# Charger.net
KiCad netlist of a schematic drawn in Altium Designer
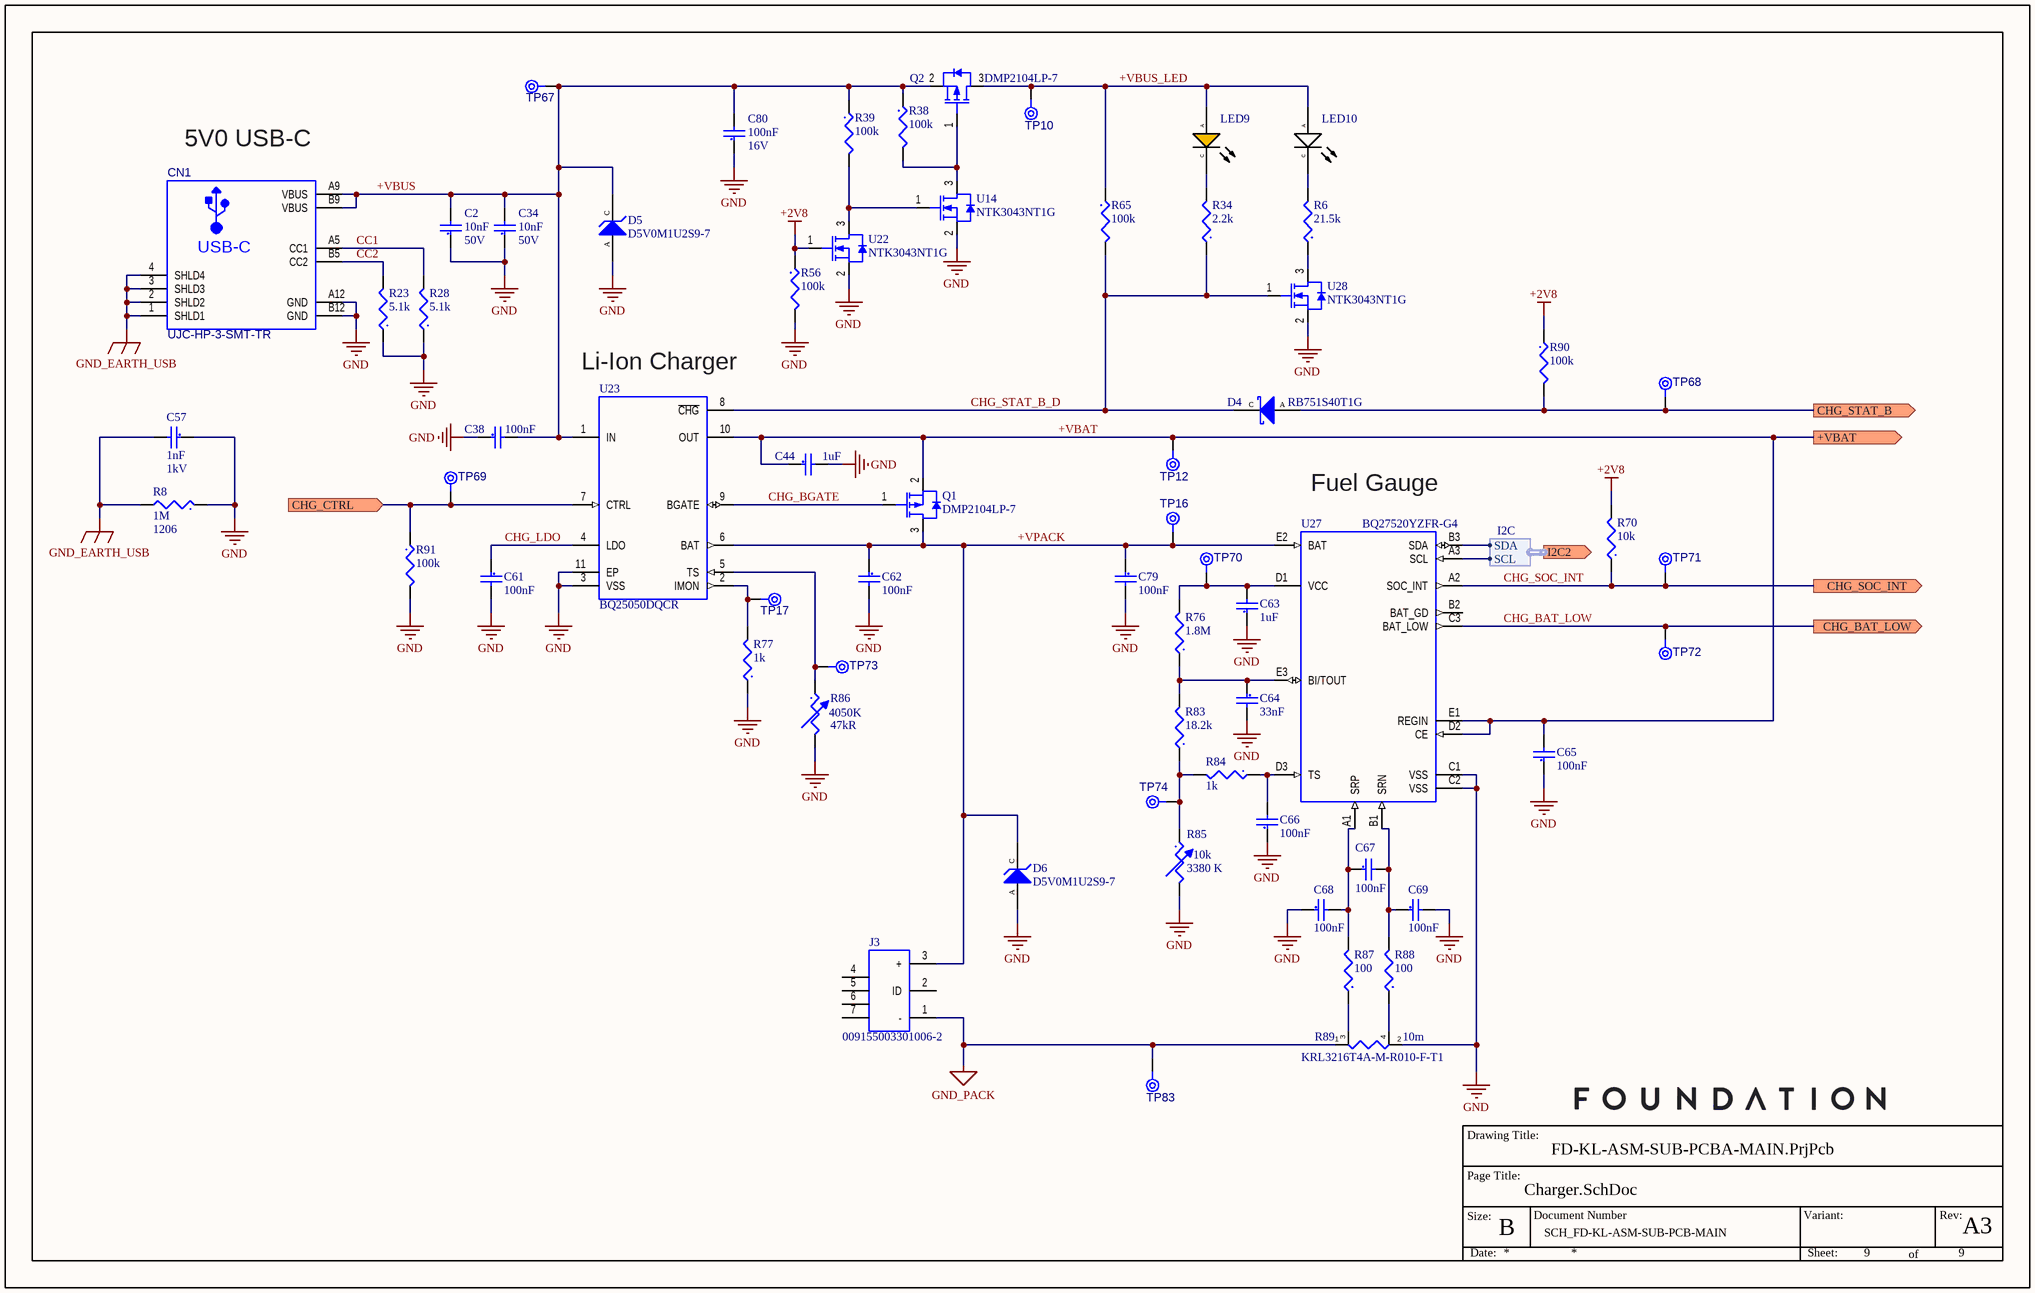
[diagram p0: Charger.SchDoc]

(export (version "E")
  (design (tool "Eeschema 10.0.6"))
  (components
    (comp (ref "C2")
      (value "CAP CER 0.01uF 50V 10% X7R 0402")
      (footprint "CAPC0402(1005)55_L")
      (description "10000pF ±10% 50V Ceramic Capacitor X7R 0402 (1005 Metric)")
      (fields
        (field (name "CAPACITANCE") "10nF")
        (field (name "TOLERANCE") "10%")
        (field (name "VOLTAGE") "50V")
      )
      (libsource (lib "Altium Concord Pro on A365") (part "CAP-NP-2"))
    )
    (comp (ref "C34")
      (value "CAP CER 0.01uF 50V 10% X7R 0402")
      (footprint "CAPC0402(1005)55_L")
      (description "10000pF ±10% 50V Ceramic Capacitor X7R 0402 (1005 Metric)")
      (fields
        (field (name "CAPACITANCE") "10nF")
        (field (name "TOLERANCE") "10%")
        (field (name "VOLTAGE") "50V")
      )
      (libsource (lib "Altium Concord Pro on A365") (part "CAP-NP-2"))
    )
    (comp (ref "C38")
      (value "CAP CER 0.1uF 16V 10% X7R 0402")
      (footprint "CAPC0402(1005)55_L")
      (description "0.1µF ±10% 16V Ceramic Capacitor X7R 0402 (1005 Metric)")
      (fields
        (field (name "CAPACITANCE") "100nF")
        (field (name "TOLERANCE") "10%")
        (field (name "VOLTAGE") "16V")
      )
      (libsource (lib "Altium Concord Pro on A365") (part "CAP-NP-2"))
    )
    (comp (ref "C44")
      (value "CAP CER 1uF 25V 10% X5R 0402")
      (footprint "CAPC0402(1005)55_L")
      (description "1uF ±10% 25V Ceramic Capacitor X5R 0402 (1005 Metric)")
      (fields (field (name "CAPACITANCE") "1uF"))
      (libsource (lib "Altium Concord Pro on A365") (part "CAP-NP-2"))
    )
    (comp (ref "C57")
      (value "CAP CER 1000pF 1000V 10% X7R 0805")
      (footprint "CAPC0805(2012)145_N")
      (description "1000pF ±10% 1000V (1kV) Ceramic Capacitor X7R 0805 (2012 Metric)")
      (fields
        (field (name "CAPACITANCE") "1nF")
        (field (name "VOLTAGE RATING (DC)") "1kV")
        (field (name "TOLERANCE") "10%")
      )
      (libsource (lib "Altium Concord Pro on A365") (part "CAP-NP-2"))
    )
    (comp (ref "C61")
      (value "CAP CER 0.1uF 16V 10% X7R 0402")
      (footprint "CAPC0402(1005)55_L")
      (description "0.1µF ±10% 16V Ceramic Capacitor X7R 0402 (1005 Metric)")
      (fields
        (field (name "CAPACITANCE") "100nF")
        (field (name "TOLERANCE") "10%")
        (field (name "VOLTAGE") "16V")
      )
      (libsource (lib "Altium Concord Pro on A365") (part "CAP-NP-2"))
    )
    (comp (ref "C62")
      (value "CAP CER 0.1uF 16V 10% X7R 0402")
      (footprint "CAPC0402(1005)55_L")
      (description "0.1µF ±10% 16V Ceramic Capacitor X7R 0402 (1005 Metric)")
      (fields
        (field (name "CAPACITANCE") "100nF")
        (field (name "TOLERANCE") "10%")
        (field (name "VOLTAGE") "16V")
      )
      (libsource (lib "Altium Concord Pro on A365") (part "CAP-NP-2"))
    )
    (comp (ref "C63")
      (value "CAP CER 1uF 25V 10% X5R 0402")
      (footprint "CAPC0402(1005)55_L")
      (description "1uF ±10% 25V Ceramic Capacitor X5R 0402 (1005 Metric)")
      (fields (field (name "CAPACITANCE") "1uF"))
      (libsource (lib "Altium Concord Pro on A365") (part "CAP-NP-2"))
    )
    (comp (ref "C64")
      (value "CAP CER 0.033uF 25V 10% X7R 0402")
      (footprint "CAPC0402(1005)55_L")
      (description "0.033µF ±10% 25V Ceramic Capacitor X7R 0402 (1005 Metric)")
      (fields (field (name "CAPACITANCE") "33nF"))
      (libsource (lib "Altium Concord Pro on A365") (part "CAP-NP-2"))
    )
    (comp (ref "C65")
      (value "CAP CER 0.1uF 16V 10% X7R 0402")
      (footprint "CAPC0402(1005)55_L")
      (description "0.1µF ±10% 16V Ceramic Capacitor X7R 0402 (1005 Metric)")
      (fields
        (field (name "CAPACITANCE") "100nF")
        (field (name "TOLERANCE") "10%")
        (field (name "VOLTAGE") "16V")
      )
      (libsource (lib "Altium Concord Pro on A365") (part "CAP-NP-2"))
    )
    (comp (ref "C66")
      (value "CAP CER 0.1uF 16V 10% X7R 0402")
      (footprint "CAPC0402(1005)55_L")
      (description "0.1µF ±10% 16V Ceramic Capacitor X7R 0402 (1005 Metric)")
      (fields
        (field (name "CAPACITANCE") "100nF")
        (field (name "TOLERANCE") "10%")
        (field (name "VOLTAGE") "16V")
      )
      (libsource (lib "Altium Concord Pro on A365") (part "CAP-NP-2"))
    )
    (comp (ref "C67")
      (value "CAP CER 0.1uF 16V 10% X7R 0402")
      (footprint "CAPC0402(1005)55_L")
      (description "0.1µF ±10% 16V Ceramic Capacitor X7R 0402 (1005 Metric)")
      (fields
        (field (name "CAPACITANCE") "100nF")
        (field (name "TOLERANCE") "10%")
        (field (name "VOLTAGE") "16V")
      )
      (libsource (lib "Altium Concord Pro on A365") (part "CAP-NP-2"))
    )
    (comp (ref "C68")
      (value "CAP CER 0.1uF 16V 10% X7R 0402")
      (footprint "CAPC0402(1005)55_L")
      (description "0.1µF ±10% 16V Ceramic Capacitor X7R 0402 (1005 Metric)")
      (fields
        (field (name "CAPACITANCE") "100nF")
        (field (name "TOLERANCE") "10%")
        (field (name "VOLTAGE") "16V")
      )
      (libsource (lib "Altium Concord Pro on A365") (part "CAP-NP-2"))
    )
    (comp (ref "C69")
      (value "CAP CER 0.1uF 16V 10% X7R 0402")
      (footprint "CAPC0402(1005)55_L")
      (description "0.1µF ±10% 16V Ceramic Capacitor X7R 0402 (1005 Metric)")
      (fields
        (field (name "CAPACITANCE") "100nF")
        (field (name "TOLERANCE") "10%")
        (field (name "VOLTAGE") "16V")
      )
      (libsource (lib "Altium Concord Pro on A365") (part "CAP-NP-2"))
    )
    (comp (ref "C79")
      (value "CAP CER 0.1uF 16V 10% X7R 0402")
      (footprint "CAPC0402(1005)55_L")
      (description "0.1µF ±10% 16V Ceramic Capacitor X7R 0402 (1005 Metric)")
      (fields
        (field (name "CAPACITANCE") "100nF")
        (field (name "TOLERANCE") "10%")
        (field (name "VOLTAGE") "16V")
      )
      (libsource (lib "Altium Concord Pro on A365") (part "CAP-NP-2"))
    )
    (comp (ref "C80")
      (value "CAP CER 0.1uF 16V 10% X7R 0402")
      (footprint "CAPC0402(1005)55_L")
      (description "0.1µF ±10% 16V Ceramic Capacitor X7R 0402 (1005 Metric)")
      (fields
        (field (name "CAPACITANCE") "100nF")
        (field (name "TOLERANCE") "10%")
        (field (name "VOLTAGE") "16V")
      )
      (libsource (lib "Altium Concord Pro on A365") (part "CAP-NP-2"))
    )
    (comp (ref "CN1")
      (value "UJC-HP-3-SMT-TR")
      (footprint "CUI - UJC-HP-3-SMT_V")
      (libsource (lib "Altium Concord Pro on A365") (part "USBC-6-4S"))
    )
    (comp (ref "D4")
      (value "RB751S40T1G")
      (footprint "ON - SOD-523_V")
      (description "Diode Schottky 30V 30mA (DC) Surface Mount SOD-523")
      (libsource (lib "Altium Concord Pro on A365") (part "DSKY-AC-2"))
    )
    (comp (ref "D5")
      (value "D5V0M1U2S9-7")
      (footprint "DIOD - SOD-923_V")
      (description "12V Clamp 9A (8/20µs) Ipp Tvs Diode Surface Mount SOD-923")
      (libsource (lib "Altium Concord Pro on A365") (part "DZEN-AC-2"))
    )
    (comp (ref "D6")
      (value "D5V0M1U2S9-7")
      (footprint "DIOD - SOD-923_V")
      (description "12V Clamp 9A (8/20µs) Ipp Tvs Diode Surface Mount SOD-923")
      (libsource (lib "Altium Concord Pro on A365") (part "DZEN-AC-2"))
    )
    (comp (ref "J3")
      (value "009155003301006-2")
      (footprint "AVX - 009155003301006_V")
      (description "3 Position Spring Battery Contact Connector Surface Mount, Right Angle")
      (libsource (lib "Altium Concord Pro on A365") (part "009155003301006-2"))
    )
    (comp (ref "LED9")
      (value "IN-S63AT5A")
      (footprint "LEDC0603(1608)65_L")
      (description "Amber 605nm LED Indication - Discrete 1.9V 0603 (1608 Metric)")
      (libsource (lib "Altium Concord Pro on A365") (part "LED-AMBER-AC-2"))
    )
    (comp (ref "LED10")
      (value "IN-S63AT5UW")
      (footprint "LEDC0603(1608)65_L")
      (description "White - LED Indication - Discrete 3V 0603 (1608 Metric)")
      (libsource (lib "Altium Concord Pro on A365") (part "LED-WHITE-AC-2"))
    )
    (comp (ref "Q1")
      (value "DMP2104LP-7")
      (footprint "DIOD - XDFN-3_V")
      (description "P-Channel 20 V 1.5A (Ta) 500mW (Ta) Surface Mount 3-DFN1411 (1.4x1.1)")
      (libsource (lib "Altium Concord Pro on A365") (part "PMOS-GSD-3"))
    )
    (comp (ref "Q2")
      (value "DMP2104LP-7")
      (footprint "DIOD - XDFN-3_V")
      (description "P-Channel 20 V 1.5A (Ta) 500mW (Ta) Surface Mount 3-DFN1411 (1.4x1.1)")
      (libsource (lib "Altium Concord Pro on A365") (part "PMOS-GSD-3"))
    )
    (comp (ref "R6")
      (value "RES 21.5K 1/16W 1% 0402")
      (footprint "RESC0402(1005)_L")
      (description "21.5 kOhms ±1% 0.063W, 1/16W Chip Resistor 0402 (1005 Metric)")
      (fields (field (name "RESISTANCE") "21.5k") (field (name "TOLERANCE") "1%"))
      (libsource (lib "Altium Concord Pro on A365") (part "RES-2"))
    )
    (comp (ref "R8")
      (value "RES 1.0M 1/4W 5% 1206")
      (footprint "RESC1206(3216)_L")
      (description "1 MOhms ±5% 0.25W, 1/4W Chip Resistor 1206 (3216 Metric) Moisture Resistant Thick Film")
      (fields
        (field (name "RESISTANCE") "1M")
        (field (name "TOLERANCE") "5%")
        (field (name "CASE CODE (IMPERIAL)") "1206")
      )
      (libsource (lib "Altium Concord Pro on A365") (part "RES-2"))
    )
    (comp (ref "R23")
      (value "RES 5.1K 1/16W 1% 0402")
      (footprint "RESC0402(1005)_L")
      (description "5.1 kOhms ±1% 0.063W, 1/16W Chip Resistor 0402 (1005 Metric)")
      (fields (field (name "RESISTANCE") "5.1k") (field (name "TOLERANCE") "1%"))
      (libsource (lib "Altium Concord Pro on A365") (part "RES-2"))
    )
    (comp (ref "R28")
      (value "RES 5.1K 1/16W 1% 0402")
      (footprint "RESC0402(1005)_L")
      (description "5.1 kOhms ±1% 0.063W, 1/16W Chip Resistor 0402 (1005 Metric)")
      (fields (field (name "RESISTANCE") "5.1k") (field (name "TOLERANCE") "1%"))
      (libsource (lib "Altium Concord Pro on A365") (part "RES-2"))
    )
    (comp (ref "R34")
      (value "RES 2.2K 1/16W 1% 0402")
      (footprint "RESC0402(1005)_L")
      (description "2.2 kOhms ±1% 0.063W, 1/16W Chip Resistor 0402 (1005 Metric)")
      (fields (field (name "RESISTANCE") "2.2k") (field (name "TOLERANCE") "1%"))
      (libsource (lib "Altium Concord Pro on A365") (part "RES-2"))
    )
    (comp (ref "R38")
      (value "RES 100K 1/16W 1% 0402")
      (footprint "RESC0402(1005)_L")
      (description "100 kOhms ±1% 0.063W, 1/16W Chip Resistor 0402 (1005 Metric) Automotive AEC-Q200 Thick Film")
      (fields (field (name "RESISTANCE") "100k") (field (name "TOLERANCE") "1%"))
      (libsource (lib "Altium Concord Pro on A365") (part "RES-2"))
    )
    (comp (ref "R39")
      (value "RES 100K 1/16W 1% 0402")
      (footprint "RESC0402(1005)_L")
      (description "100 kOhms ±1% 0.063W, 1/16W Chip Resistor 0402 (1005 Metric) Automotive AEC-Q200 Thick Film")
      (fields (field (name "RESISTANCE") "100k") (field (name "TOLERANCE") "1%"))
      (libsource (lib "Altium Concord Pro on A365") (part "RES-2"))
    )
    (comp (ref "R56")
      (value "RES 100K 1/16W 1% 0402")
      (footprint "RESC0402(1005)_L")
      (description "100 kOhms ±1% 0.063W, 1/16W Chip Resistor 0402 (1005 Metric) Automotive AEC-Q200 Thick Film")
      (fields (field (name "RESISTANCE") "100k") (field (name "TOLERANCE") "1%"))
      (libsource (lib "Altium Concord Pro on A365") (part "RES-2"))
    )
    (comp (ref "R65")
      (value "RES 100K 1/16W 1% 0402")
      (footprint "RESC0402(1005)_L")
      (description "100 kOhms ±1% 0.063W, 1/16W Chip Resistor 0402 (1005 Metric) Automotive AEC-Q200 Thick Film")
      (fields (field (name "RESISTANCE") "100k") (field (name "TOLERANCE") "1%"))
      (libsource (lib "Altium Concord Pro on A365") (part "RES-2"))
    )
    (comp (ref "R70")
      (value "RES 10K 1/16W 1% 0402")
      (footprint "RESC0402(1005)_L")
      (description "10 kOhms ±1% 0.063W, 1/16W Chip Resistor 0402 (1005 Metric)")
      (fields (field (name "RESISTANCE") "10k") (field (name "TOLERANCE") "1%"))
      (libsource (lib "Altium Concord Pro on A365") (part "RES-2"))
    )
    (comp (ref "R76")
      (value "RES 1.8M 1/16W 1% 0402")
      (footprint "RESC0402(1005)_L")
      (description "1.8 MOhms ±1% 0.063W, 1/16W Chip Resistor 0402 (1005 Metric)")
      (fields (field (name "RESISTANCE") "1.8M") (field (name "TOLERANCE") "1%"))
      (libsource (lib "Altium Concord Pro on A365") (part "RES-2"))
    )
    (comp (ref "R77")
      (value "RES 1.0K 1/16W 1% 0402")
      (footprint "RESC0402(1005)_L")
      (description "1 kOhms ±0.5% 0.063W, 1/16W Chip Resistor 0402 (1005 Metric) Automotive AEC-Q200 Thin Film")
      (fields (field (name "RESISTANCE") "1k") (field (name "TOLERANCE") "0.5%"))
      (libsource (lib "Altium Concord Pro on A365") (part "RES-2"))
    )
    (comp (ref "R83")
      (value "RES 18.2K 1/16W 1% 0402")
      (footprint "RESC0402(1005)_L")
      (description "18.2 kOhms ±1% 0.063W, 1/16W Chip Resistor 0402 (1005 Metric)")
      (fields (field (name "RESISTANCE") "18.2k") (field (name "TOLERANCE") "1%"))
      (libsource (lib "Altium Concord Pro on A365") (part "RES-2"))
    )
    (comp (ref "R84")
      (value "RES 1.0K 1/16W 1% 0402")
      (footprint "RESC0402(1005)_L")
      (description "1 kOhms ±0.5% 0.063W, 1/16W Chip Resistor 0402 (1005 Metric) Automotive AEC-Q200 Thin Film")
      (fields (field (name "RESISTANCE") "1k") (field (name "TOLERANCE") "0.5%"))
      (libsource (lib "Altium Concord Pro on A365") (part "RES-2"))
    )
    (comp (ref "R85")
      (value "NTCG103JF103FT1")
      (footprint "RESC0402(1005)_L")
      (description "NTC Thermistor 10k 0402 (1005 Metric)")
      (fields (field (name "RESISTANCE") "10k") (field (name "B CONSTANT [25/50°C]") "3380 K"))
      (libsource (lib "Altium Concord Pro on A365") (part "RES-ADJ-2"))
    )
    (comp (ref "R86")
      (value "NCP15WB473F03RC")
      (footprint "RESC0402(1005)_L")
      (description "NTC Thermistor 47k 0402 (1005 Metric)")
      (fields
        (field (name "RESISTANCE") "47kR")
        (field (name "B CONSTANT [25/50°C]") "4050K")
        (field (name "TOLERANCE") "1%")
      )
      (libsource (lib "Altium Concord Pro on A365") (part "RES-ADJ-2"))
    )
    (comp (ref "R87")
      (value "RES 100 OHM 1/16W 1% 0402")
      (footprint "RESC0402(1005)_L")
      (description "100 Ohms ±1% 0.063W, 1/16W Chip Resistor 0402 (1005 Metric)  Thick Film")
      (fields (field (name "RESISTANCE") "100") (field (name "TOLERANCE") "1%"))
      (libsource (lib "Altium Concord Pro on A365") (part "RES-2"))
    )
    (comp (ref "R88")
      (value "RES 100 OHM 1/16W 1% 0402")
      (footprint "RESC0402(1005)_L")
      (description "100 Ohms ±1% 0.063W, 1/16W Chip Resistor 0402 (1005 Metric)  Thick Film")
      (fields (field (name "RESISTANCE") "100") (field (name "TOLERANCE") "1%"))
      (libsource (lib "Altium Concord Pro on A365") (part "RES-2"))
    )
    (comp (ref "R89")
      (value "KRL3216T4A-M-R010-F-T1")
      (footprint "Susumu - KRL3216T4A_V")
      (description "Fixed Resistor, Metal Foil, 1W, 0.01ohm, 1% +/-Tol, 35ppm/Cel, Surface Mount, 1206")
      (fields (field (name "RESISTANCE") "10m") (field (name "TOLERANCE") "1%"))
      (libsource (lib "Altium Concord Pro on A365") (part "RES-4-13-24"))
    )
    (comp (ref "R90")
      (value "RES 100K 1/16W 1% 0402")
      (footprint "RESC0402(1005)_L")
      (description "100 kOhms ±1% 0.063W, 1/16W Chip Resistor 0402 (1005 Metric) Automotive AEC-Q200 Thick Film")
      (fields (field (name "RESISTANCE") "100k") (field (name "TOLERANCE") "1%"))
      (libsource (lib "Altium Concord Pro on A365") (part "RES-2"))
    )
    (comp (ref "R91")
      (value "RES 100K 1/16W 1% 0402")
      (footprint "RESC0402(1005)_L")
      (description "100 kOhms ±1% 0.063W, 1/16W Chip Resistor 0402 (1005 Metric) Automotive AEC-Q200 Thick Film")
      (fields (field (name "RESISTANCE") "100k") (field (name "TOLERANCE") "1%"))
      (libsource (lib "Altium Concord Pro on A365") (part "RES-2"))
    )
    (comp (ref "TP10")
      (value "TPAD8R")
      (footprint "TP08R")
      (description "0.8mm round")
      (libsource (lib "Altium Concord Pro on A365") (part "TP-R-1"))
    )
    (comp (ref "TP12")
      (value "TPAD8R")
      (footprint "TP08R")
      (description "0.8mm round")
      (libsource (lib "Altium Concord Pro on A365") (part "TP-R-1"))
    )
    (comp (ref "TP16")
      (value "TPAD8R")
      (footprint "TP08R")
      (description "0.8mm round")
      (libsource (lib "Altium Concord Pro on A365") (part "TP-R-1"))
    )
    (comp (ref "TP17")
      (value "TPAD8R")
      (footprint "TP08R")
      (description "0.8mm round")
      (libsource (lib "Altium Concord Pro on A365") (part "TP-R-1"))
    )
    (comp (ref "TP67")
      (value "TPAD8R")
      (footprint "TP08R")
      (description "0.8mm round")
      (libsource (lib "Altium Concord Pro on A365") (part "TP-R-1"))
    )
    (comp (ref "TP68")
      (value "TPAD8R")
      (footprint "TP08R")
      (description "0.8mm round")
      (libsource (lib "Altium Concord Pro on A365") (part "TP-R-1"))
    )
    (comp (ref "TP69")
      (value "TPAD8R")
      (footprint "TP08R")
      (description "0.8mm round")
      (libsource (lib "Altium Concord Pro on A365") (part "TP-R-1"))
    )
    (comp (ref "TP70")
      (value "TPAD8R")
      (footprint "TP08R")
      (description "0.8mm round")
      (libsource (lib "Altium Concord Pro on A365") (part "TP-R-1"))
    )
    (comp (ref "TP71")
      (value "TPAD8R")
      (footprint "TP08R")
      (description "0.8mm round")
      (libsource (lib "Altium Concord Pro on A365") (part "TP-R-1"))
    )
    (comp (ref "TP72")
      (value "TPAD8R")
      (footprint "TP08R")
      (description "0.8mm round")
      (libsource (lib "Altium Concord Pro on A365") (part "TP-R-1"))
    )
    (comp (ref "TP73")
      (value "TPAD8R")
      (footprint "TP08R")
      (description "0.8mm round")
      (libsource (lib "Altium Concord Pro on A365") (part "TP-R-1"))
    )
    (comp (ref "TP74")
      (value "TPAD8R")
      (footprint "TP08R")
      (description "0.8mm round")
      (libsource (lib "Altium Concord Pro on A365") (part "TP-R-1"))
    )
    (comp (ref "TP83")
      (value "TPAD8R")
      (footprint "TP08R")
      (description "0.8mm round")
      (libsource (lib "Altium Concord Pro on A365") (part "TP-R-1"))
    )
    (comp (ref "U14")
      (value "NTK3043NT1G")
      (footprint "SOT-723-3(40)_N")
      (description "N-Channel 20V 210mA (Ta) 310mW (Ta) Surface Mount SOT-723")
      (libsource (lib "Altium Concord Pro on A365") (part "NMOS-GSD-3"))
    )
    (comp (ref "U22")
      (value "NTK3043NT1G")
      (footprint "SOT-723-3(40)_N")
      (description "N-Channel 20V 210mA (Ta) 310mW (Ta) Surface Mount SOT-723")
      (libsource (lib "Altium Concord Pro on A365") (part "NMOS-GSD-3"))
    )
    (comp (ref "U23")
      (value "BQ25050DQCR")
      (footprint "TI - WSON-DQC-10_V")
      (description "Charger IC Lithium Ion 10-WSON (3x2)")
      (libsource (lib "Altium Concord Pro on A365") (part "SYM-IC-0151"))
    )
    (comp (ref "U27")
      (value "BQ27520YZFR-G4")
      (footprint "TI - DSBGA-YZF-15_V")
      (description "Battery Battery Monitor IC Lithium Ion 15-DSBGA")
      (libsource (lib "Altium Concord Pro on A365") (part "BQ27520YZFR-G4"))
    )
    (comp (ref "U28")
      (value "NTK3043NT1G")
      (footprint "SOT-723-3(40)_N")
      (description "N-Channel 20V 210mA (Ta) 310mW (Ta) Surface Mount SOT-723")
      (libsource (lib "Altium Concord Pro on A365") (part "NMOS-GSD-3"))
    )
  )
  (nets
    (net (code "2") (name "+2V8") (class "Default")
      (node (ref "R56") (pin "1") (pinfunction "1_1") (pintype "passive"))
      (node (ref "R70") (pin "2") (pinfunction "2_2") (pintype "passive"))
      (node (ref "R90") (pin "1") (pinfunction "1_1") (pintype "passive"))
      (node (ref "U22") (pin "1") (pinfunction "G_1") (pintype "passive"))
    )
    (net (code "3") (name "/+VBAT") (class "Default")
      (node (ref "C44") (pin "1") (pinfunction "1_1") (pintype "passive"))
      (node (ref "C65") (pin "2") (pinfunction "2_2") (pintype "passive"))
      (node (ref "Q1") (pin "2") (pinfunction "SOURCE_2") (pintype "passive"))
      (node (ref "TP12") (pin "1") (pinfunction "TP_1") (pintype "passive"))
      (node (ref "U23") (pin "10") (pinfunction "OUT_10") (pintype "power_in"))
      (node (ref "U27") (pin "D2") (pinfunction "CE_D2") (pintype "input"))
      (node (ref "U27") (pin "E1") (pinfunction "REGIN_E1") (pintype "passive"))
    )
    (net (code "4") (name "/+VBUS") (class "Default")
      (node (ref "C2") (pin "2") (pinfunction "2_2") (pintype "passive"))
      (node (ref "C34") (pin "2") (pinfunction "2_2") (pintype "passive"))
      (node (ref "C38") (pin "2") (pinfunction "2_2") (pintype "passive"))
      (node (ref "C80") (pin "2") (pinfunction "2_2") (pintype "passive"))
      (node (ref "CN1") (pin "A9") (pinfunction "VBUS_A9") (pintype "passive"))
      (node (ref "CN1") (pin "B9") (pinfunction "VBUS_B9") (pintype "passive"))
      (node (ref "D5") (pin "C") (pinfunction "C_C") (pintype "passive"))
      (node (ref "Q2") (pin "2") (pinfunction "SOURCE_2") (pintype "passive"))
      (node (ref "R38") (pin "1") (pinfunction "1_1") (pintype "passive"))
      (node (ref "R39") (pin "1") (pinfunction "1_1") (pintype "passive"))
      (node (ref "TP67") (pin "1") (pinfunction "TP_1") (pintype "passive"))
      (node (ref "U23") (pin "1") (pinfunction "IN_1") (pintype "power_in"))
    )
    (net (code "5") (name "/+VBUS_LED") (class "Default")
      (node (ref "LED10") (pin "A") (pinfunction "A_A") (pintype "passive"))
      (node (ref "LED9") (pin "A") (pinfunction "A_A") (pintype "passive"))
      (node (ref "Q2") (pin "3") (pinfunction "DRAIN_3") (pintype "passive"))
      (node (ref "R65") (pin "1") (pinfunction "1_1") (pintype "passive"))
      (node (ref "TP10") (pin "1") (pinfunction "TP_1") (pintype "passive"))
    )
    (net (code "6") (name "/+VPACK") (class "Default")
      (node (ref "C62") (pin "1") (pinfunction "1_1") (pintype "passive"))
      (node (ref "C79") (pin "1") (pinfunction "1_1") (pintype "passive"))
      (node (ref "D6") (pin "C") (pinfunction "C_C") (pintype "passive"))
      (node (ref "J3") (pin "3") (pinfunction "+_3") (pintype "passive"))
      (node (ref "Q1") (pin "3") (pinfunction "DRAIN_3") (pintype "passive"))
      (node (ref "TP16") (pin "1") (pinfunction "TP_1") (pintype "passive"))
      (node (ref "U23") (pin "6") (pinfunction "BAT_6") (pintype "output"))
      (node (ref "U27") (pin "E2") (pinfunction "BAT_E2") (pintype "input"))
    )
    (net (code "7") (name "/CC1") (class "Default")
      (node (ref "CN1") (pin "A5") (pinfunction "CC1_A5") (pintype "passive"))
      (node (ref "R28") (pin "2") (pinfunction "2_2") (pintype "passive"))
    )
    (net (code "8") (name "/CC2") (class "Default")
      (node (ref "CN1") (pin "B5") (pinfunction "CC2_B5") (pintype "passive"))
      (node (ref "R23") (pin "2") (pinfunction "2_2") (pintype "passive"))
    )
    (net (code "9") (name "/CHG_BAT_LOW") (class "Default")
      (node (ref "TP72") (pin "1") (pinfunction "TP_1") (pintype "passive"))
      (node (ref "U27") (pin "C3") (pinfunction "BAT_LOW_C3") (pintype "output"))
    )
    (net (code "10") (name "/CHG_BGATE") (class "Default")
      (node (ref "Q1") (pin "1") (pinfunction "GATE_1") (pintype "passive"))
      (node (ref "U23") (pin "9") (pinfunction "BGATE_9") (pintype "bidirectional"))
    )
    (net (code "11") (name "/CHG_CTRL") (class "Default")
      (node (ref "R91") (pin "1") (pinfunction "1_1") (pintype "passive"))
      (node (ref "TP69") (pin "1") (pinfunction "TP_1") (pintype "passive"))
      (node (ref "U23") (pin "7") (pinfunction "CTRL_7") (pintype "input"))
    )
    (net (code "12") (name "/CHG_LDO") (class "Default")
      (node (ref "C61") (pin "1") (pinfunction "1_1") (pintype "passive"))
      (node (ref "U23") (pin "4") (pinfunction "LDO_4") (pintype "power_in"))
    )
    (net (code "13") (name "/CHG_SOC_INT") (class "Default")
      (node (ref "R70") (pin "1") (pinfunction "1_1") (pintype "passive"))
      (node (ref "TP71") (pin "1") (pinfunction "TP_1") (pintype "passive"))
      (node (ref "U27") (pin "A2") (pinfunction "SOC_INT_A2") (pintype "output"))
    )
    (net (code "14") (name "/CHG_STAT_B") (class "Default")
      (node (ref "D4") (pin "A") (pinfunction "A_A") (pintype "passive"))
      (node (ref "R90") (pin "2") (pinfunction "2_2") (pintype "passive"))
      (node (ref "TP68") (pin "1") (pinfunction "TP_1") (pintype "passive"))
    )
    (net (code "15") (name "/CHG_STAT_B_D") (class "Default")
      (node (ref "D4") (pin "C") (pinfunction "C_C") (pintype "passive"))
      (node (ref "R34") (pin "1") (pinfunction "1_1") (pintype "passive"))
      (node (ref "R65") (pin "2") (pinfunction "2_2") (pintype "passive"))
      (node (ref "U23") (pin "8") (pinfunction "~{CHG}_8") (pintype "tri_state"))
      (node (ref "U28") (pin "1") (pinfunction "G_1") (pintype "passive"))
    )
    (net (code "16") (name "/SCL") (class "Default")
      (node (ref "U27") (pin "A3") (pinfunction "SCL_A3") (pintype "input"))
    )
    (net (code "17") (name "/SDA") (class "Default")
      (node (ref "U27") (pin "B3") (pinfunction "SDA_B3") (pintype "bidirectional"))
    )
    (net (code "19") (name "GND") (class "Default")
      (node (ref "C2") (pin "1") (pinfunction "1_1") (pintype "passive"))
      (node (ref "C34") (pin "1") (pinfunction "1_1") (pintype "passive"))
      (node (ref "C38") (pin "1") (pinfunction "1_1") (pintype "passive"))
      (node (ref "C44") (pin "2") (pinfunction "2_2") (pintype "passive"))
      (node (ref "C57") (pin "1") (pinfunction "1_1") (pintype "passive"))
      (node (ref "C61") (pin "2") (pinfunction "2_2") (pintype "passive"))
      (node (ref "C62") (pin "2") (pinfunction "2_2") (pintype "passive"))
      (node (ref "C63") (pin "1") (pinfunction "1_1") (pintype "passive"))
      (node (ref "C64") (pin "2") (pinfunction "2_2") (pintype "passive"))
      (node (ref "C65") (pin "1") (pinfunction "1_1") (pintype "passive"))
      (node (ref "C66") (pin "1") (pinfunction "1_1") (pintype "passive"))
      (node (ref "C68") (pin "1") (pinfunction "1_1") (pintype "passive"))
      (node (ref "C69") (pin "2") (pinfunction "2_2") (pintype "passive"))
      (node (ref "C79") (pin "2") (pinfunction "2_2") (pintype "passive"))
      (node (ref "C80") (pin "1") (pinfunction "1_1") (pintype "passive"))
      (node (ref "CN1") (pin "A12") (pinfunction "GND_A12") (pintype "passive"))
      (node (ref "CN1") (pin "B12") (pinfunction "GND_B12") (pintype "passive"))
      (node (ref "D5") (pin "A") (pinfunction "A_A") (pintype "passive"))
      (node (ref "D6") (pin "A") (pinfunction "A_A") (pintype "passive"))
      (node (ref "R23") (pin "1") (pinfunction "1_1") (pintype "passive"))
      (node (ref "R28") (pin "1") (pinfunction "1_1") (pintype "passive"))
      (node (ref "R56") (pin "2") (pinfunction "2_2") (pintype "passive"))
      (node (ref "R77") (pin "1") (pinfunction "1_1") (pintype "passive"))
      (node (ref "R8") (pin "1") (pinfunction "1_1") (pintype "passive"))
      (node (ref "R85") (pin "2") (pinfunction "2_2") (pintype "passive"))
      (node (ref "R86") (pin "2") (pinfunction "2_2") (pintype "passive"))
      (node (ref "R89") (pin "2") (pinfunction "I2_2") (pintype "passive"))
      (node (ref "R91") (pin "2") (pinfunction "2_2") (pintype "passive"))
      (node (ref "U14") (pin "2") (pinfunction "S_2") (pintype "passive"))
      (node (ref "U22") (pin "2") (pinfunction "S_2") (pintype "passive"))
      (node (ref "U23") (pin "11") (pinfunction "EP_11") (pintype "power_in"))
      (node (ref "U23") (pin "3") (pinfunction "VSS_3") (pintype "power_in"))
      (node (ref "U27") (pin "C1") (pinfunction "VSS_C1") (pintype "passive"))
      (node (ref "U27") (pin "C2") (pinfunction "VSS_C2") (pintype "passive"))
      (node (ref "U28") (pin "2") (pinfunction "S_2") (pintype "passive"))
    )
    (net (code "20") (name "GND_EARTH_USB") (class "Default")
      (node (ref "C57") (pin "2") (pinfunction "2_2") (pintype "passive"))
      (node (ref "CN1") (pin "1") (pinfunction "SHLD1_1") (pintype "passive"))
      (node (ref "CN1") (pin "2") (pinfunction "SHLD2_2") (pintype "passive"))
      (node (ref "CN1") (pin "3") (pinfunction "SHLD3_3") (pintype "passive"))
      (node (ref "CN1") (pin "4") (pinfunction "SHLD4_4") (pintype "passive"))
      (node (ref "R8") (pin "2") (pinfunction "2_2") (pintype "passive"))
    )
    (net (code "21") (name "GND_PACK") (class "Default")
      (node (ref "J3") (pin "1") (pinfunction "-_1") (pintype "passive"))
      (node (ref "R89") (pin "1") (pinfunction "I1_1") (pintype "passive"))
      (node (ref "TP83") (pin "1") (pinfunction "TP_1") (pintype "passive"))
    )
    (net (code "22") (name "Net-(LED9-PadC)") (class "Default")
      (node (ref "LED9") (pin "C") (pinfunction "C_C") (pintype "passive"))
      (node (ref "R34") (pin "2") (pinfunction "2_2") (pintype "passive"))
    )
    (net (code "23") (name "Net-(LED10-PadC)") (class "Default")
      (node (ref "LED10") (pin "C") (pinfunction "C_C") (pintype "passive"))
      (node (ref "R6") (pin "2") (pinfunction "2_2") (pintype "passive"))
    )
    (net (code "24") (name "Net-(Q2-GATE)") (class "Default")
      (node (ref "Q2") (pin "1") (pinfunction "GATE_1") (pintype "passive"))
      (node (ref "R38") (pin "2") (pinfunction "2_2") (pintype "passive"))
      (node (ref "U14") (pin "3") (pinfunction "D_3") (pintype "passive"))
    )
    (net (code "25") (name "Net-(R89-E1)") (class "Default")
      (node (ref "R87") (pin "1") (pinfunction "1_1") (pintype "passive"))
      (node (ref "R89") (pin "3") (pinfunction "E1_3") (pintype "passive"))
    )
    (net (code "26") (name "Net-(R89-E2)") (class "Default")
      (node (ref "R88") (pin "1") (pinfunction "1_1") (pintype "passive"))
      (node (ref "R89") (pin "4") (pinfunction "E2_4") (pintype "passive"))
    )
    (net (code "27") (name "Net-(TP17-TP)") (class "Default")
      (node (ref "R77") (pin "2") (pinfunction "2_2") (pintype "passive"))
      (node (ref "TP17") (pin "1") (pinfunction "TP_1") (pintype "passive"))
      (node (ref "U23") (pin "2") (pinfunction "IMON_2") (pintype "output"))
    )
    (net (code "28") (name "Net-(TP70-TP)") (class "Default")
      (node (ref "C63") (pin "2") (pinfunction "2_2") (pintype "passive"))
      (node (ref "R76") (pin "2") (pinfunction "2_2") (pintype "passive"))
      (node (ref "TP70") (pin "1") (pinfunction "TP_1") (pintype "passive"))
      (node (ref "U27") (pin "D1") (pinfunction "VCC_D1") (pintype "passive"))
    )
    (net (code "29") (name "Net-(TP73-TP)") (class "Default")
      (node (ref "R86") (pin "1") (pinfunction "1_1") (pintype "passive"))
      (node (ref "TP73") (pin "1") (pinfunction "TP_1") (pintype "passive"))
      (node (ref "U23") (pin "5") (pinfunction "TS_5") (pintype "input"))
    )
    (net (code "30") (name "Net-(TP74-TP)") (class "Default")
      (node (ref "R83") (pin "1") (pinfunction "1_1") (pintype "passive"))
      (node (ref "R84") (pin "2") (pinfunction "2_2") (pintype "passive"))
      (node (ref "R85") (pin "1") (pinfunction "1_1") (pintype "passive"))
      (node (ref "TP74") (pin "1") (pinfunction "TP_1") (pintype "passive"))
    )
    (net (code "31") (name "Net-(U14-G)") (class "Default")
      (node (ref "R39") (pin "2") (pinfunction "2_2") (pintype "passive"))
      (node (ref "U14") (pin "1") (pinfunction "G_1") (pintype "passive"))
      (node (ref "U22") (pin "3") (pinfunction "D_3") (pintype "passive"))
    )
    (net (code "32") (name "Net-(U27-BI{slash}TOUT)") (class "Default")
      (node (ref "C64") (pin "1") (pinfunction "1_1") (pintype "passive"))
      (node (ref "R76") (pin "1") (pinfunction "1_1") (pintype "passive"))
      (node (ref "R83") (pin "2") (pinfunction "2_2") (pintype "passive"))
      (node (ref "U27") (pin "E3") (pinfunction "BI/TOUT_E3") (pintype "bidirectional"))
    )
    (net (code "33") (name "Net-(U27-SRN)") (class "Default")
      (node (ref "C67") (pin "2") (pinfunction "2_2") (pintype "passive"))
      (node (ref "C69") (pin "1") (pinfunction "1_1") (pintype "passive"))
      (node (ref "R88") (pin "2") (pinfunction "2_2") (pintype "passive"))
      (node (ref "U27") (pin "B1") (pinfunction "SRN_B1") (pintype "input"))
    )
    (net (code "34") (name "Net-(U27-SRP)") (class "Default")
      (node (ref "C67") (pin "1") (pinfunction "1_1") (pintype "passive"))
      (node (ref "C68") (pin "2") (pinfunction "2_2") (pintype "passive"))
      (node (ref "R87") (pin "2") (pinfunction "2_2") (pintype "passive"))
      (node (ref "U27") (pin "A1") (pinfunction "SRP_A1") (pintype "input"))
    )
    (net (code "35") (name "Net-(U27-TS)") (class "Default")
      (node (ref "C66") (pin "2") (pinfunction "2_2") (pintype "passive"))
      (node (ref "R84") (pin "1") (pinfunction "1_1") (pintype "passive"))
      (node (ref "U27") (pin "D3") (pinfunction "TS_D3") (pintype "input"))
    )
    (net (code "36") (name "Net-(U28-D)") (class "Default")
      (node (ref "R6") (pin "1") (pinfunction "1_1") (pintype "passive"))
      (node (ref "U28") (pin "3") (pinfunction "D_3") (pintype "passive"))
    )
    (net (code "37") (name "unconnected-(J3-ID-Pad2)") (class "Default")
      (node (ref "J3") (pin "2") (pinfunction "ID_2") (pintype "passive"))
    )
    (net (code "38") (name "unconnected-(J3-Pad4)") (class "Default")
      (node (ref "J3") (pin "4") (pinfunction "4_4") (pintype "passive"))
    )
    (net (code "39") (name "unconnected-(J3-Pad5)") (class "Default")
      (node (ref "J3") (pin "5") (pinfunction "5_5") (pintype "passive"))
    )
    (net (code "40") (name "unconnected-(J3-Pad6)") (class "Default")
      (node (ref "J3") (pin "6") (pinfunction "6_6") (pintype "passive"))
    )
    (net (code "41") (name "unconnected-(J3-Pad7)") (class "Default")
      (node (ref "J3") (pin "7") (pinfunction "7_7") (pintype "passive"))
    )
    (net (code "42") (name "unconnected-(U27-BAT_GD-PadB2)") (class "Default")
      (node (ref "U27") (pin "B2") (pinfunction "BAT_GD_B2") (pintype "output"))
    )
  )
)
